# lora1121m.net
KiCad netlist of a schematic drawn in Altium Designer
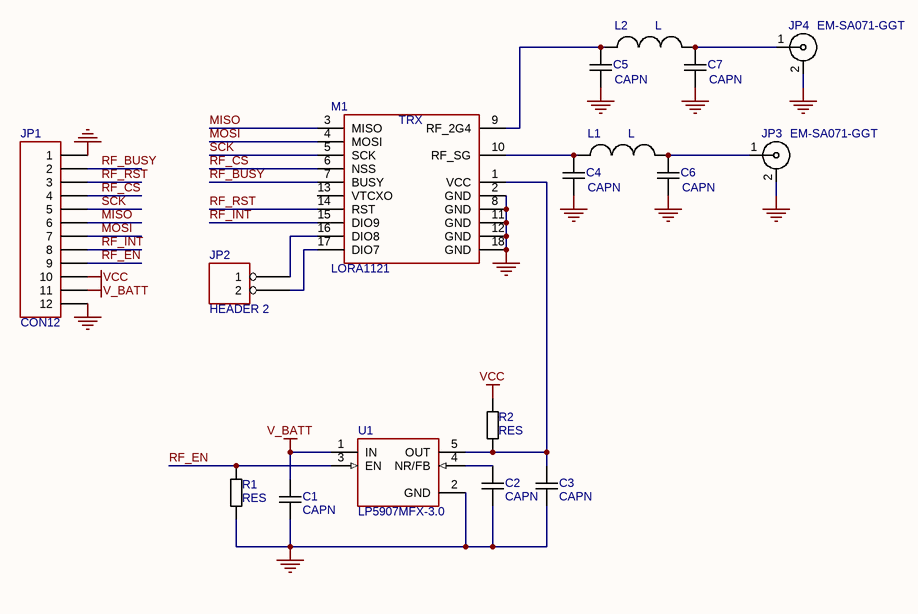
[diagram p0: lora1121m.SchDoc]

(export (version "E")
  (design (tool "Eeschema 10.0.6"))
  (components
    (comp (ref "C1")
      (value "CAPN")
      (footprint "C-0805")
      (fields (field (name "VOLTAGE") "50V"))
      (libsource (lib "Passive") (part "CAPN"))
    )
    (comp (ref "C2")
      (value "CAPN")
      (footprint "C-0603")
      (fields (field (name "VOLTAGE") "50V"))
      (libsource (lib "Passive") (part "CAPN"))
    )
    (comp (ref "C3")
      (value "CAPN")
      (footprint "C-0805")
      (fields (field (name "VOLTAGE") "50V"))
      (libsource (lib "Passive") (part "CAPN"))
    )
    (comp (ref "C4")
      (value "CAPN")
      (footprint "C-0603")
      (fields (field (name "VOLTAGE") "50V"))
      (libsource (lib "Passive") (part "CAPN"))
    )
    (comp (ref "C5")
      (value "CAPN")
      (footprint "C-0603")
      (fields (field (name "VOLTAGE") "50V"))
      (libsource (lib "Passive") (part "CAPN"))
    )
    (comp (ref "C6")
      (value "CAPN")
      (footprint "C-0603")
      (fields (field (name "VOLTAGE") "50V"))
      (libsource (lib "Passive") (part "CAPN"))
    )
    (comp (ref "C7")
      (value "CAPN")
      (footprint "C-0603")
      (fields (field (name "VOLTAGE") "50V"))
      (libsource (lib "Passive") (part "CAPN"))
    )
    (comp (ref "JP1")
      (value "CON12")
      (footprint "PBS1-12R")
      (description "Connector")
      (libsource (lib "Connectors") (part "CON12"))
    )
    (comp (ref "JP2")
      (value "HEADER 2")
      (footprint "PLS1-2")
      (libsource (lib "Connectors") (part "HEADER 2"))
    )
    (comp (ref "JP3")
      (value "EM-SA071-GGT")
      (footprint "SMA_F_EDGE")
      (description "SMA Female R/A PCB Mount")
      (libsource (lib "Connectors") (part "SMA"))
    )
    (comp (ref "JP4")
      (value "EM-SA071-GGT")
      (footprint "SMA_F_EDGE")
      (description "SMA Female R/A PCB Mount")
      (libsource (lib "Connectors") (part "SMA"))
    )
    (comp (ref "L1") (value "L") (footprint "L-0603") (libsource (lib "Passive") (part "L")))
    (comp (ref "L2") (value "L") (footprint "L-0603") (libsource (lib "Passive") (part "L")))
    (comp (ref "M1")
      (value "LORA1121")
      (footprint "LORA1121")
      (libsource (lib "RFmodules") (part "LORA1121"))
    )
    (comp (ref "R1") (value "RES") (footprint "R-0603") (libsource (lib "Passive") (part "RES")))
    (comp (ref "R2") (value "RES") (footprint "R-0603") (libsource (lib "Passive") (part "RES")))
    (comp (ref "U1")
      (value "LP5907MFX-3.0")
      (footprint "SOT-23-5")
      (description "250mA Low-Dropout Regulator")
      (libsource (lib "ICs") (part "LP5907"))
    )
  )
  (nets
    (net (code "1") (name "/MISO") (class "Default")
      (node (ref "JP1") (pin "6") (pinfunction "6_6") (pintype "passive"))
      (node (ref "M1") (pin "3") (pinfunction "MISO_3") (pintype "passive"))
    )
    (net (code "2") (name "/MOSI") (class "Default")
      (node (ref "JP1") (pin "7") (pinfunction "7_7") (pintype "passive"))
      (node (ref "M1") (pin "4") (pinfunction "MOSI_4") (pintype "passive"))
    )
    (net (code "3") (name "/RF_BUSY") (class "Default")
      (node (ref "JP1") (pin "2") (pinfunction "2_2") (pintype "passive"))
      (node (ref "M1") (pin "7") (pinfunction "BUSY_7") (pintype "passive"))
    )
    (net (code "4") (name "/RF_CS") (class "Default")
      (node (ref "JP1") (pin "4") (pinfunction "4_4") (pintype "passive"))
      (node (ref "M1") (pin "6") (pinfunction "NSS_6") (pintype "passive"))
    )
    (net (code "5") (name "/RF_EN") (class "Default")
      (node (ref "JP1") (pin "9") (pinfunction "9_9") (pintype "passive"))
      (node (ref "R1") (pin "2") (pinfunction "2_2") (pintype "passive"))
      (node (ref "U1") (pin "3") (pinfunction "EN_3") (pintype "input"))
    )
    (net (code "6") (name "/RF_INT") (class "Default")
      (node (ref "JP1") (pin "8") (pinfunction "8_8") (pintype "passive"))
      (node (ref "M1") (pin "15") (pinfunction "DIO9_15") (pintype "passive"))
    )
    (net (code "7") (name "/RF_RST") (class "Default")
      (node (ref "JP1") (pin "3") (pinfunction "3_3") (pintype "passive"))
      (node (ref "M1") (pin "14") (pinfunction "RST_14") (pintype "passive"))
    )
    (net (code "8") (name "/SCK") (class "Default")
      (node (ref "JP1") (pin "5") (pinfunction "5_5") (pintype "passive"))
      (node (ref "M1") (pin "5") (pinfunction "SCK_5") (pintype "passive"))
    )
    (net (code "9") (name "GND") (class "Default")
      (node (ref "C1") (pin "2") (pinfunction "2_2") (pintype "passive"))
      (node (ref "C2") (pin "2") (pinfunction "2_2") (pintype "passive"))
      (node (ref "C3") (pin "2") (pinfunction "2_2") (pintype "passive"))
      (node (ref "C4") (pin "2") (pinfunction "2_2") (pintype "passive"))
      (node (ref "C5") (pin "2") (pinfunction "2_2") (pintype "passive"))
      (node (ref "C6") (pin "2") (pinfunction "2_2") (pintype "passive"))
      (node (ref "C7") (pin "2") (pinfunction "2_2") (pintype "passive"))
      (node (ref "JP1") (pin "1") (pinfunction "1_1") (pintype "passive"))
      (node (ref "JP1") (pin "12") (pinfunction "12_12") (pintype "passive"))
      (node (ref "JP3") (pin "2") (pinfunction "2_2") (pintype "passive"))
      (node (ref "JP4") (pin "2") (pinfunction "2_2") (pintype "passive"))
      (node (ref "M1") (pin "11") (pinfunction "GND_11") (pintype "passive"))
      (node (ref "M1") (pin "12") (pinfunction "GND_12") (pintype "passive"))
      (node (ref "M1") (pin "18") (pinfunction "GND_18") (pintype "passive"))
      (node (ref "M1") (pin "2") (pinfunction "GND_2") (pintype "passive"))
      (node (ref "M1") (pin "8") (pinfunction "GND_8") (pintype "passive"))
      (node (ref "R1") (pin "1") (pinfunction "1_1") (pintype "passive"))
      (node (ref "U1") (pin "2") (pinfunction "GND_2") (pintype "power_in"))
    )
    (net (code "10") (name "Net-(C6-Pad1)") (class "Default")
      (node (ref "C6") (pin "1") (pinfunction "1_1") (pintype "passive"))
      (node (ref "JP3") (pin "1") (pinfunction "1_1") (pintype "passive"))
      (node (ref "L1") (pin "2") (pinfunction "2_2") (pintype "passive"))
    )
    (net (code "11") (name "Net-(C7-Pad1)") (class "Default")
      (node (ref "C7") (pin "1") (pinfunction "1_1") (pintype "passive"))
      (node (ref "JP4") (pin "1") (pinfunction "1_1") (pintype "passive"))
      (node (ref "L2") (pin "2") (pinfunction "2_2") (pintype "passive"))
    )
    (net (code "12") (name "Net-(M1-DIO7)") (class "Default")
      (node (ref "JP2") (pin "2") (pinfunction "2_2") (pintype "passive"))
      (node (ref "M1") (pin "17") (pinfunction "DIO7_17") (pintype "passive"))
    )
    (net (code "13") (name "Net-(M1-DIO8)") (class "Default")
      (node (ref "JP2") (pin "1") (pinfunction "1_1") (pintype "passive"))
      (node (ref "M1") (pin "16") (pinfunction "DIO8_16") (pintype "passive"))
    )
    (net (code "14") (name "Net-(M1-RF_2G4)") (class "Default")
      (node (ref "C5") (pin "1") (pinfunction "1_1") (pintype "passive"))
      (node (ref "L2") (pin "1") (pinfunction "1_1") (pintype "passive"))
      (node (ref "M1") (pin "9") (pinfunction "RF_2G4_9") (pintype "passive"))
    )
    (net (code "15") (name "Net-(M1-RF_SG)") (class "Default")
      (node (ref "C4") (pin "1") (pinfunction "1_1") (pintype "passive"))
      (node (ref "L1") (pin "1") (pinfunction "1_1") (pintype "passive"))
      (node (ref "M1") (pin "10") (pinfunction "RF_SG_10") (pintype "passive"))
    )
    (net (code "16") (name "Net-(M1-VCC)") (class "Default")
      (node (ref "C3") (pin "1") (pinfunction "1_1") (pintype "passive"))
      (node (ref "M1") (pin "1") (pinfunction "VCC_1") (pintype "passive"))
      (node (ref "R2") (pin "1") (pinfunction "1_1") (pintype "passive"))
      (node (ref "U1") (pin "5") (pinfunction "OUT_5") (pintype "power_in"))
    )
    (net (code "17") (name "Net-(U1-NR{slash}FB)") (class "Default")
      (node (ref "C2") (pin "1") (pinfunction "1_1") (pintype "passive"))
      (node (ref "U1") (pin "4") (pinfunction "NR/FB_4") (pintype "input"))
    )
    (net (code "18") (name "VCC") (class "Default")
      (node (ref "JP1") (pin "10") (pinfunction "10_10") (pintype "passive"))
      (node (ref "R2") (pin "2") (pinfunction "2_2") (pintype "passive"))
    )
    (net (code "19") (name "V_BATT") (class "Default")
      (node (ref "C1") (pin "1") (pinfunction "1_1") (pintype "passive"))
      (node (ref "JP1") (pin "11") (pinfunction "11_11") (pintype "passive"))
      (node (ref "U1") (pin "1") (pinfunction "IN_1") (pintype "power_in"))
    )
    (net (code "20") (name "unconnected-(M1-VTCXO-Pad13)") (class "Default")
      (node (ref "M1") (pin "13") (pinfunction "VTCXO_13") (pintype "passive"))
    )
  )
)
